# PowerManagement.net
KiCad netlist of a schematic drawn in Altium Designer
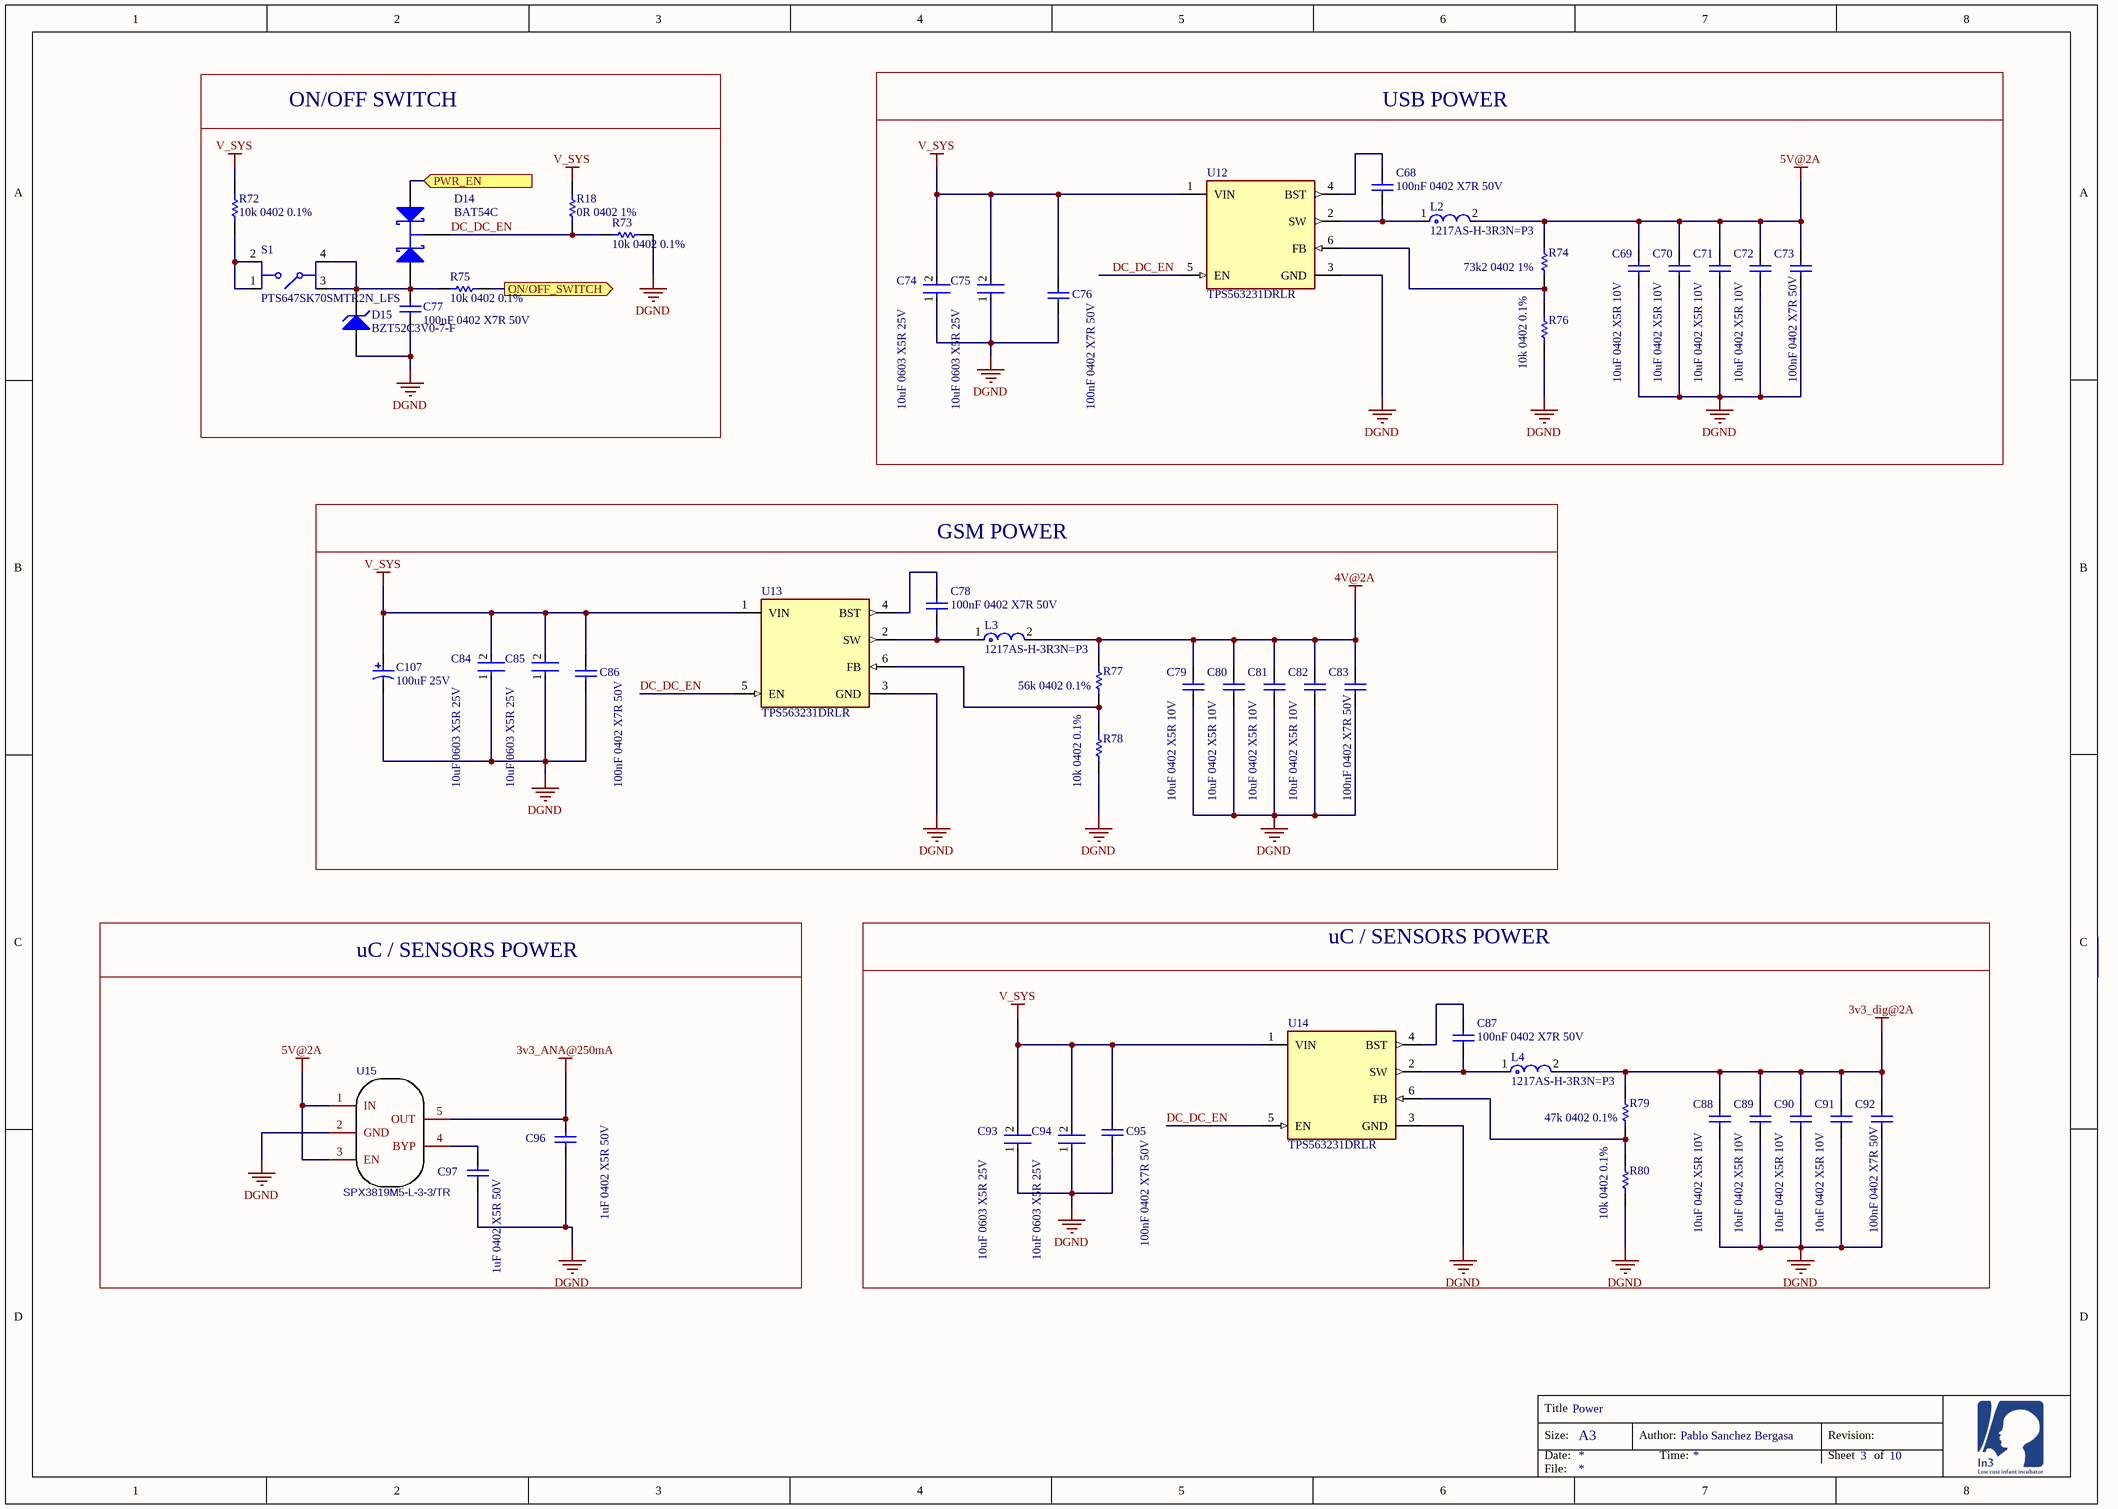
[diagram p0: PowerManagement.SchDoc]

(export (version "E")
  (design (tool "Eeschema 10.0.6"))
  (components
    (comp (ref "C68")
      (value "100nF 0402 X7R 50V")
      (footprint "CAPC1005X55X25NL5T10")
      (libsource (lib "Altium Content Vault") (part "CAP-NP-2"))
    )
    (comp (ref "C69")
      (value "10uF 0402 X5R 10V")
      (footprint "CAPC1005X55X25NL5T10")
      (libsource (lib "Altium Content Vault") (part "CAP-NP-2"))
    )
    (comp (ref "C70")
      (value "10uF 0402 X5R 10V")
      (footprint "CAPC1005X55X25NL5T10")
      (libsource (lib "Altium Content Vault") (part "CAP-NP-2"))
    )
    (comp (ref "C71")
      (value "10uF 0402 X5R 10V")
      (footprint "CAPC1005X55X25NL5T10")
      (libsource (lib "Altium Content Vault") (part "CAP-NP-2"))
    )
    (comp (ref "C72")
      (value "10uF 0402 X5R 10V")
      (footprint "CAPC1005X55X25NL5T10")
      (libsource (lib "Altium Content Vault") (part "CAP-NP-2"))
    )
    (comp (ref "C73")
      (value "100nF 0402 X7R 50V")
      (footprint "CAPC1005X55X25NL5T10")
      (libsource (lib "Altium Content Vault") (part "CAP-NP-2"))
    )
    (comp (ref "C74")
      (value "10uF 0603 X5R 25V")
      (footprint "FP-GRM188-0_2-IPC_B")
      (libsource (lib "Altium Content Vault") (part "11868f565c42a9108669ba33697ecf6"))
    )
    (comp (ref "C75")
      (value "10uF 0603 X5R 25V")
      (footprint "FP-GRM188-0_2-IPC_B")
      (libsource (lib "Altium Content Vault") (part "11868f565c42a9108669ba33697ecf6"))
    )
    (comp (ref "C76")
      (value "100nF 0402 X7R 50V")
      (footprint "CAPC1005X55X25NL5T10")
      (libsource (lib "Altium Content Vault") (part "CAP-NP-2"))
    )
    (comp (ref "C77")
      (value "100nF 0402 X7R 50V")
      (footprint "CAPC1005X55X25NL5T10")
      (libsource (lib "Altium Content Vault") (part "CAP-NP-2"))
    )
    (comp (ref "C78")
      (value "100nF 0402 X7R 50V")
      (footprint "CAPC1005X55X25NL5T10")
      (libsource (lib "Altium Content Vault") (part "CAP-NP-2"))
    )
    (comp (ref "C79")
      (value "10uF 0402 X5R 10V")
      (footprint "CAPC1005X55X25NL5T10")
      (libsource (lib "Altium Content Vault") (part "CAP-NP-2"))
    )
    (comp (ref "C80")
      (value "10uF 0402 X5R 10V")
      (footprint "CAPC1005X55X25NL5T10")
      (libsource (lib "Altium Content Vault") (part "CAP-NP-2"))
    )
    (comp (ref "C81")
      (value "10uF 0402 X5R 10V")
      (footprint "CAPC1005X55X25NL5T10")
      (libsource (lib "Altium Content Vault") (part "CAP-NP-2"))
    )
    (comp (ref "C82")
      (value "10uF 0402 X5R 10V")
      (footprint "CAPC1005X55X25NL5T10")
      (libsource (lib "Altium Content Vault") (part "CAP-NP-2"))
    )
    (comp (ref "C83")
      (value "100nF 0402 X7R 50V")
      (footprint "CAPC1005X55X25NL5T10")
      (libsource (lib "Altium Content Vault") (part "CAP-NP-2"))
    )
    (comp (ref "C84")
      (value "10uF 0603 X5R 25V")
      (footprint "FP-GRM188-0_2-IPC_B")
      (libsource (lib "Altium Content Vault") (part "11868f565c42a9108669ba33697ecf6"))
    )
    (comp (ref "C85")
      (value "10uF 0603 X5R 25V")
      (footprint "FP-GRM188-0_2-IPC_B")
      (libsource (lib "Altium Content Vault") (part "11868f565c42a9108669ba33697ecf6"))
    )
    (comp (ref "C86")
      (value "100nF 0402 X7R 50V")
      (footprint "CAPC1005X55X25NL5T10")
      (libsource (lib "Altium Content Vault") (part "CAP-NP-2"))
    )
    (comp (ref "C87")
      (value "100nF 0402 X7R 50V")
      (footprint "CAPC1005X55X25NL5T10")
      (libsource (lib "Altium Content Vault") (part "CAP-NP-2"))
    )
    (comp (ref "C88")
      (value "10uF 0402 X5R 10V")
      (footprint "CAPC1005X55X25NL5T10")
      (libsource (lib "Altium Content Vault") (part "CAP-NP-2"))
    )
    (comp (ref "C89")
      (value "10uF 0402 X5R 10V")
      (footprint "CAPC1005X55X25NL5T10")
      (libsource (lib "Altium Content Vault") (part "CAP-NP-2"))
    )
    (comp (ref "C90")
      (value "10uF 0402 X5R 10V")
      (footprint "CAPC1005X55X25NL5T10")
      (libsource (lib "Altium Content Vault") (part "CAP-NP-2"))
    )
    (comp (ref "C91")
      (value "10uF 0402 X5R 10V")
      (footprint "CAPC1005X55X25NL5T10")
      (libsource (lib "Altium Content Vault") (part "CAP-NP-2"))
    )
    (comp (ref "C92")
      (value "100nF 0402 X7R 50V")
      (footprint "CAPC1005X55X25NL5T10")
      (libsource (lib "Altium Content Vault") (part "CAP-NP-2"))
    )
    (comp (ref "C93")
      (value "10uF 0603 X5R 25V")
      (footprint "FP-GRM188-0_2-IPC_B")
      (libsource (lib "Altium Content Vault") (part "11868f565c42a9108669ba33697ecf6"))
    )
    (comp (ref "C94")
      (value "10uF 0603 X5R 25V")
      (footprint "FP-GRM188-0_2-IPC_B")
      (libsource (lib "Altium Content Vault") (part "11868f565c42a9108669ba33697ecf6"))
    )
    (comp (ref "C95")
      (value "100nF 0402 X7R 50V")
      (footprint "CAPC1005X55X25NL5T10")
      (libsource (lib "Altium Content Vault") (part "CAP-NP-2"))
    )
    (comp (ref "C96")
      (value "1uF 0402 X5R 50V")
      (footprint "CAPC1005X55X25NL5T10")
      (libsource (lib "Altium Content Vault") (part "CAP-NP-2"))
    )
    (comp (ref "C97")
      (value "1uF 0402 X5R 50V")
      (footprint "CAPC1005X55X25NL5T10")
      (libsource (lib "Altium Content Vault") (part "CAP-NP-2"))
    )
    (comp (ref "C107")
      (value "100uF 25V")
      (footprint "CAPAE7067X55L")
      (fields (field (name "MANUFACTURER") "Nichicon"))
      (libsource (lib "Altium Content Vault") (part "CAP-P-2"))
    )
    (comp (ref "D14")
      (value "BAT54C")
      (footprint "NXP-SOT23-3_V")
      (description "Schottky Barrier Diode, 30 V, 2 uA, -55 to 150 degC, 3-Pin SOT23, RoHS, Tape and Reel")
      (fields (field (name "MANUFACTURER") "NXP Semiconductors"))
      (libsource (lib "Altium Content Vault") (part "NXP-DSKY_A1A2K3-3"))
    )
    (comp (ref "D15")
      (value "BZT52C3V0-7-F")
      (footprint "DIOD-SOD123_V")
      (description "Surface Mount Zener Diode, 3 V, -65 to 150 degC, 2-Pin SOD123, RoHS, Tape and Reel")
      (fields (field (name "MANUFACTURER") "DiodesIncorporated"))
      (libsource (lib "Altium Content Vault") (part "DZEN-AK-2"))
    )
    (comp (ref "L2")
      (value "1217AS-H-3R3N=P3")
      (footprint "FP-DEM8045C-MFG")
      (description "Shielded Wirewound Inductor 3.3uH 30% 6800mA 0.0144Ω SMD")
      (fields (field (name "TOLERANCE") "30%"))
      (libsource (lib "Altium Content Vault") (part "4cc4b267dca4c8e51f7102f422741d8"))
    )
    (comp (ref "L3")
      (value "1217AS-H-3R3N=P3")
      (footprint "FP-DEM8045C-MFG")
      (description "Shielded Wirewound Inductor 3.3uH 30% 6800mA 0.0144Ω SMD")
      (fields (field (name "TOLERANCE") "30%"))
      (libsource (lib "Altium Content Vault") (part "4cc4b267dca4c8e51f7102f422741d8"))
    )
    (comp (ref "L4")
      (value "1217AS-H-3R3N=P3")
      (footprint "FP-DEM8045C-MFG")
      (description "Shielded Wirewound Inductor 3.3uH 30% 6800mA 0.0144Ω SMD")
      (fields (field (name "TOLERANCE") "30%"))
      (libsource (lib "Altium Content Vault") (part "4cc4b267dca4c8e51f7102f422741d8"))
    )
    (comp (ref "R18")
      (value "0R 0402 1%")
      (footprint "RESC1005X40X25ML05T10")
      (libsource (lib "Altium Content Vault") (part "RES"))
    )
    (comp (ref "R72")
      (value "10k 0402 0.1%")
      (footprint "RESC1005X40X25ML05T10")
      (libsource (lib "Altium Content Vault") (part "RES"))
    )
    (comp (ref "R73")
      (value "10k 0402 0.1%")
      (footprint "RESC1005X40X25ML05T10")
      (libsource (lib "Altium Content Vault") (part "RES"))
    )
    (comp (ref "R74")
      (value "73k2 0402 1%")
      (footprint "RESC1005X40X25ML05T10")
      (fields (field (name "MANUFACTURER") "Yageo / Phycomp"))
      (libsource (lib "Altium Content Vault") (part "RES"))
    )
    (comp (ref "R75")
      (value "10k 0402 0.1%")
      (footprint "RESC1005X40X25ML05T10")
      (libsource (lib "Altium Content Vault") (part "RES"))
    )
    (comp (ref "R76")
      (value "10k 0402 0.1%")
      (footprint "RESC1005X40X25ML05T10")
      (libsource (lib "Altium Content Vault") (part "RES"))
    )
    (comp (ref "R77")
      (value "56k 0402 0.1%")
      (footprint "RESC1005X40X25ML05T10")
      (libsource (lib "Altium Content Vault") (part "RES"))
    )
    (comp (ref "R78")
      (value "10k 0402 0.1%")
      (footprint "RESC1005X40X25ML05T10")
      (libsource (lib "Altium Content Vault") (part "RES"))
    )
    (comp (ref "R79")
      (value "47k 0402 0.1%")
      (footprint "RESC1005X40X25ML05T10")
      (libsource (lib "Altium Content Vault") (part "RES"))
    )
    (comp (ref "R80")
      (value "10k 0402 0.1%")
      (footprint "RESC1005X40X25ML05T10")
      (libsource (lib "Altium Content Vault") (part "RES"))
    )
    (comp (ref "S1")
      (value "PTS647SK70SMTR2N_LFS")
      (footprint "SamacSys:PTS647SK70SMTR2NLFS")
      (description "Switch (4-Pin Push)")
      (fields (field (name "MANUFACTURER_PART_NUMBER") "PTS647SK70SMTR2N LFS"))
      (libsource (lib "*") (part "PTS647SK70SMTR2N_LFS"))
    )
    (comp (ref "U12")
      (value "TPS563231DRLR")
      (footprint "FP-DRL0006A-MFG")
      (description "POWER MANAGEMENT")
      (libsource (lib "Altium Content Vault") (part "4d860df4d3ea23b1aa54a495432cd8a"))
    )
    (comp (ref "U13")
      (value "TPS563231DRLR")
      (footprint "FP-DRL0006A-MFG")
      (description "POWER MANAGEMENT")
      (libsource (lib "Altium Content Vault") (part "4d860df4d3ea23b1aa54a495432cd8a"))
    )
    (comp (ref "U14")
      (value "TPS563231DRLR")
      (footprint "FP-DRL0006A-MFG")
      (description "POWER MANAGEMENT")
      (libsource (lib "Altium Content Vault") (part "4d860df4d3ea23b1aa54a495432cd8a"))
    )
    (comp (ref "U15")
      (value "SPX3819M5-L-3-3/TR")
      (footprint "SOT-23-5_L3.0-W1.7-P0.95-LS2.8-BR")
      (fields (field (name "BOM_SUPPLIER PART") "C9055"))
      (libsource (lib "LCSC") (part "SPX3819M5-L-3-3/TR"))
    )
  )
  (nets
    (net (code "1") (name "/DC_DC_EN") (class "Default")
      (node (ref "D14") (pin "3") (pinfunction "K_3") (pintype "passive"))
      (node (ref "R18") (pin "2") (pinfunction "2_2") (pintype "passive"))
      (node (ref "R73") (pin "2") (pinfunction "2_2") (pintype "passive"))
      (node (ref "U12") (pin "5") (pinfunction "EN_5") (pintype "input"))
      (node (ref "U13") (pin "5") (pinfunction "EN_5") (pintype "input"))
      (node (ref "U14") (pin "5") (pinfunction "EN_5") (pintype "input"))
    )
    (net (code "2") (name "/ON{slash}OFF_SWITCH") (class "Default")
      (node (ref "R75") (pin "1") (pinfunction "1_1") (pintype "passive"))
    )
    (net (code "3") (name "/PWR_EN") (class "Default")
      (node (ref "D14") (pin "2") (pinfunction "A_2") (pintype "passive"))
    )
    (net (code "4") (name "3v3_ANA@250mA") (class "Default")
      (node (ref "C96") (pin "2") (pinfunction "2_2") (pintype "passive"))
      (node (ref "U15") (pin "5") (pinfunction "OUT_5") (pintype "passive"))
    )
    (net (code "5") (name "3v3_dig@2A") (class "Default")
      (node (ref "C88") (pin "2") (pinfunction "2_2") (pintype "passive"))
      (node (ref "C89") (pin "2") (pinfunction "2_2") (pintype "passive"))
      (node (ref "C90") (pin "2") (pinfunction "2_2") (pintype "passive"))
      (node (ref "C91") (pin "2") (pinfunction "2_2") (pintype "passive"))
      (node (ref "C92") (pin "2") (pinfunction "2_2") (pintype "passive"))
      (node (ref "L4") (pin "2") (pinfunction "2_2") (pintype "passive"))
      (node (ref "R79") (pin "2") (pinfunction "2_2") (pintype "passive"))
    )
    (net (code "6") (name "4V@2A") (class "Default")
      (node (ref "C79") (pin "2") (pinfunction "2_2") (pintype "passive"))
      (node (ref "C80") (pin "2") (pinfunction "2_2") (pintype "passive"))
      (node (ref "C81") (pin "2") (pinfunction "2_2") (pintype "passive"))
      (node (ref "C82") (pin "2") (pinfunction "2_2") (pintype "passive"))
      (node (ref "C83") (pin "2") (pinfunction "2_2") (pintype "passive"))
      (node (ref "L3") (pin "2") (pinfunction "2_2") (pintype "passive"))
      (node (ref "R77") (pin "2") (pinfunction "2_2") (pintype "passive"))
    )
    (net (code "7") (name "5V@2A") (class "Default")
      (node (ref "C69") (pin "2") (pinfunction "2_2") (pintype "passive"))
      (node (ref "C70") (pin "2") (pinfunction "2_2") (pintype "passive"))
      (node (ref "C71") (pin "2") (pinfunction "2_2") (pintype "passive"))
      (node (ref "C72") (pin "2") (pinfunction "2_2") (pintype "passive"))
      (node (ref "C73") (pin "2") (pinfunction "2_2") (pintype "passive"))
      (node (ref "L2") (pin "2") (pinfunction "2_2") (pintype "passive"))
      (node (ref "R74") (pin "2") (pinfunction "2_2") (pintype "passive"))
      (node (ref "U15") (pin "1") (pinfunction "IN_1") (pintype "passive"))
      (node (ref "U15") (pin "3") (pinfunction "EN_3") (pintype "passive"))
    )
    (net (code "8") (name "DGND") (class "Default")
      (node (ref "C107") (pin "2") (pinfunction "2_2") (pintype "passive"))
      (node (ref "C69") (pin "1") (pinfunction "1_1") (pintype "passive"))
      (node (ref "C70") (pin "1") (pinfunction "1_1") (pintype "passive"))
      (node (ref "C71") (pin "1") (pinfunction "1_1") (pintype "passive"))
      (node (ref "C72") (pin "1") (pinfunction "1_1") (pintype "passive"))
      (node (ref "C73") (pin "1") (pinfunction "1_1") (pintype "passive"))
      (node (ref "C74") (pin "1") (pinfunction "1_1") (pintype "passive"))
      (node (ref "C75") (pin "1") (pinfunction "1_1") (pintype "passive"))
      (node (ref "C76") (pin "1") (pinfunction "1_1") (pintype "passive"))
      (node (ref "C77") (pin "1") (pinfunction "1_1") (pintype "passive"))
      (node (ref "C79") (pin "1") (pinfunction "1_1") (pintype "passive"))
      (node (ref "C80") (pin "1") (pinfunction "1_1") (pintype "passive"))
      (node (ref "C81") (pin "1") (pinfunction "1_1") (pintype "passive"))
      (node (ref "C82") (pin "1") (pinfunction "1_1") (pintype "passive"))
      (node (ref "C83") (pin "1") (pinfunction "1_1") (pintype "passive"))
      (node (ref "C84") (pin "1") (pinfunction "1_1") (pintype "passive"))
      (node (ref "C85") (pin "1") (pinfunction "1_1") (pintype "passive"))
      (node (ref "C86") (pin "1") (pinfunction "1_1") (pintype "passive"))
      (node (ref "C88") (pin "1") (pinfunction "1_1") (pintype "passive"))
      (node (ref "C89") (pin "1") (pinfunction "1_1") (pintype "passive"))
      (node (ref "C90") (pin "1") (pinfunction "1_1") (pintype "passive"))
      (node (ref "C91") (pin "1") (pinfunction "1_1") (pintype "passive"))
      (node (ref "C92") (pin "1") (pinfunction "1_1") (pintype "passive"))
      (node (ref "C93") (pin "1") (pinfunction "1_1") (pintype "passive"))
      (node (ref "C94") (pin "1") (pinfunction "1_1") (pintype "passive"))
      (node (ref "C95") (pin "1") (pinfunction "1_1") (pintype "passive"))
      (node (ref "C96") (pin "1") (pinfunction "1_1") (pintype "passive"))
      (node (ref "C97") (pin "1") (pinfunction "1_1") (pintype "passive"))
      (node (ref "D15") (pin "1") (pinfunction "A_1") (pintype "passive"))
      (node (ref "R73") (pin "1") (pinfunction "1_1") (pintype "passive"))
      (node (ref "R76") (pin "1") (pinfunction "1_1") (pintype "passive"))
      (node (ref "R78") (pin "1") (pinfunction "1_1") (pintype "passive"))
      (node (ref "R80") (pin "1") (pinfunction "1_1") (pintype "passive"))
      (node (ref "U12") (pin "3") (pinfunction "GND_3") (pintype "power_in"))
      (node (ref "U13") (pin "3") (pinfunction "GND_3") (pintype "power_in"))
      (node (ref "U14") (pin "3") (pinfunction "GND_3") (pintype "power_in"))
      (node (ref "U15") (pin "2") (pinfunction "GND_2") (pintype "passive"))
    )
    (net (code "9") (name "Net-(D15-K)") (class "Default")
      (node (ref "C77") (pin "2") (pinfunction "2_2") (pintype "passive"))
      (node (ref "D14") (pin "1") (pinfunction "A_1") (pintype "passive"))
      (node (ref "D15") (pin "2") (pinfunction "K_2") (pintype "passive"))
      (node (ref "R75") (pin "2") (pinfunction "2_2") (pintype "passive"))
      (node (ref "S1") (pin "3") (pinfunction "COM_1_3") (pintype "passive"))
      (node (ref "S1") (pin "4") (pinfunction "COM_2_4") (pintype "passive"))
    )
    (net (code "10") (name "Net-(S1-NO_1)") (class "Default")
      (node (ref "R72") (pin "2") (pinfunction "2_2") (pintype "passive"))
      (node (ref "S1") (pin "1") (pinfunction "NO_1_1") (pintype "passive"))
      (node (ref "S1") (pin "2") (pinfunction "NO_2_2") (pintype "passive"))
    )
    (net (code "11") (name "Net-(U12-BST)") (class "Default")
      (node (ref "C68") (pin "2") (pinfunction "2_2") (pintype "passive"))
      (node (ref "U12") (pin "4") (pinfunction "BST_4") (pintype "output"))
    )
    (net (code "12") (name "Net-(U12-FB)") (class "Default")
      (node (ref "R74") (pin "1") (pinfunction "1_1") (pintype "passive"))
      (node (ref "R76") (pin "2") (pinfunction "2_2") (pintype "passive"))
      (node (ref "U12") (pin "6") (pinfunction "FB_6") (pintype "input"))
    )
    (net (code "13") (name "Net-(U12-SW)") (class "Default")
      (node (ref "C68") (pin "1") (pinfunction "1_1") (pintype "passive"))
      (node (ref "L2") (pin "1") (pinfunction "1_1") (pintype "passive"))
      (node (ref "U12") (pin "2") (pinfunction "SW_2") (pintype "output"))
    )
    (net (code "14") (name "Net-(U13-BST)") (class "Default")
      (node (ref "C78") (pin "2") (pinfunction "2_2") (pintype "passive"))
      (node (ref "U13") (pin "4") (pinfunction "BST_4") (pintype "output"))
    )
    (net (code "15") (name "Net-(U13-FB)") (class "Default")
      (node (ref "R77") (pin "1") (pinfunction "1_1") (pintype "passive"))
      (node (ref "R78") (pin "2") (pinfunction "2_2") (pintype "passive"))
      (node (ref "U13") (pin "6") (pinfunction "FB_6") (pintype "input"))
    )
    (net (code "16") (name "Net-(U13-SW)") (class "Default")
      (node (ref "C78") (pin "1") (pinfunction "1_1") (pintype "passive"))
      (node (ref "L3") (pin "1") (pinfunction "1_1") (pintype "passive"))
      (node (ref "U13") (pin "2") (pinfunction "SW_2") (pintype "output"))
    )
    (net (code "17") (name "Net-(U14-BST)") (class "Default")
      (node (ref "C87") (pin "2") (pinfunction "2_2") (pintype "passive"))
      (node (ref "U14") (pin "4") (pinfunction "BST_4") (pintype "output"))
    )
    (net (code "18") (name "Net-(U14-FB)") (class "Default")
      (node (ref "R79") (pin "1") (pinfunction "1_1") (pintype "passive"))
      (node (ref "R80") (pin "2") (pinfunction "2_2") (pintype "passive"))
      (node (ref "U14") (pin "6") (pinfunction "FB_6") (pintype "input"))
    )
    (net (code "19") (name "Net-(U14-SW)") (class "Default")
      (node (ref "C87") (pin "1") (pinfunction "1_1") (pintype "passive"))
      (node (ref "L4") (pin "1") (pinfunction "1_1") (pintype "passive"))
      (node (ref "U14") (pin "2") (pinfunction "SW_2") (pintype "output"))
    )
    (net (code "20") (name "Net-(U15-BYP)") (class "Default")
      (node (ref "C97") (pin "2") (pinfunction "2_2") (pintype "passive"))
      (node (ref "U15") (pin "4") (pinfunction "BYP_4") (pintype "passive"))
    )
    (net (code "21") (name "V_SYS") (class "Default")
      (node (ref "C107") (pin "1") (pinfunction "1_1") (pintype "passive"))
      (node (ref "C74") (pin "2") (pinfunction "2_2") (pintype "passive"))
      (node (ref "C75") (pin "2") (pinfunction "2_2") (pintype "passive"))
      (node (ref "C76") (pin "2") (pinfunction "2_2") (pintype "passive"))
      (node (ref "C84") (pin "2") (pinfunction "2_2") (pintype "passive"))
      (node (ref "C85") (pin "2") (pinfunction "2_2") (pintype "passive"))
      (node (ref "C86") (pin "2") (pinfunction "2_2") (pintype "passive"))
      (node (ref "C93") (pin "2") (pinfunction "2_2") (pintype "passive"))
      (node (ref "C94") (pin "2") (pinfunction "2_2") (pintype "passive"))
      (node (ref "C95") (pin "2") (pinfunction "2_2") (pintype "passive"))
      (node (ref "R18") (pin "1") (pinfunction "1_1") (pintype "passive"))
      (node (ref "R72") (pin "1") (pinfunction "1_1") (pintype "passive"))
      (node (ref "U12") (pin "1") (pinfunction "VIN_1") (pintype "power_in"))
      (node (ref "U13") (pin "1") (pinfunction "VIN_1") (pintype "power_in"))
      (node (ref "U14") (pin "1") (pinfunction "VIN_1") (pintype "power_in"))
    )
  )
)
